# Geiger_v3.net
KiCad netlist of a schematic drawn in EAGLE
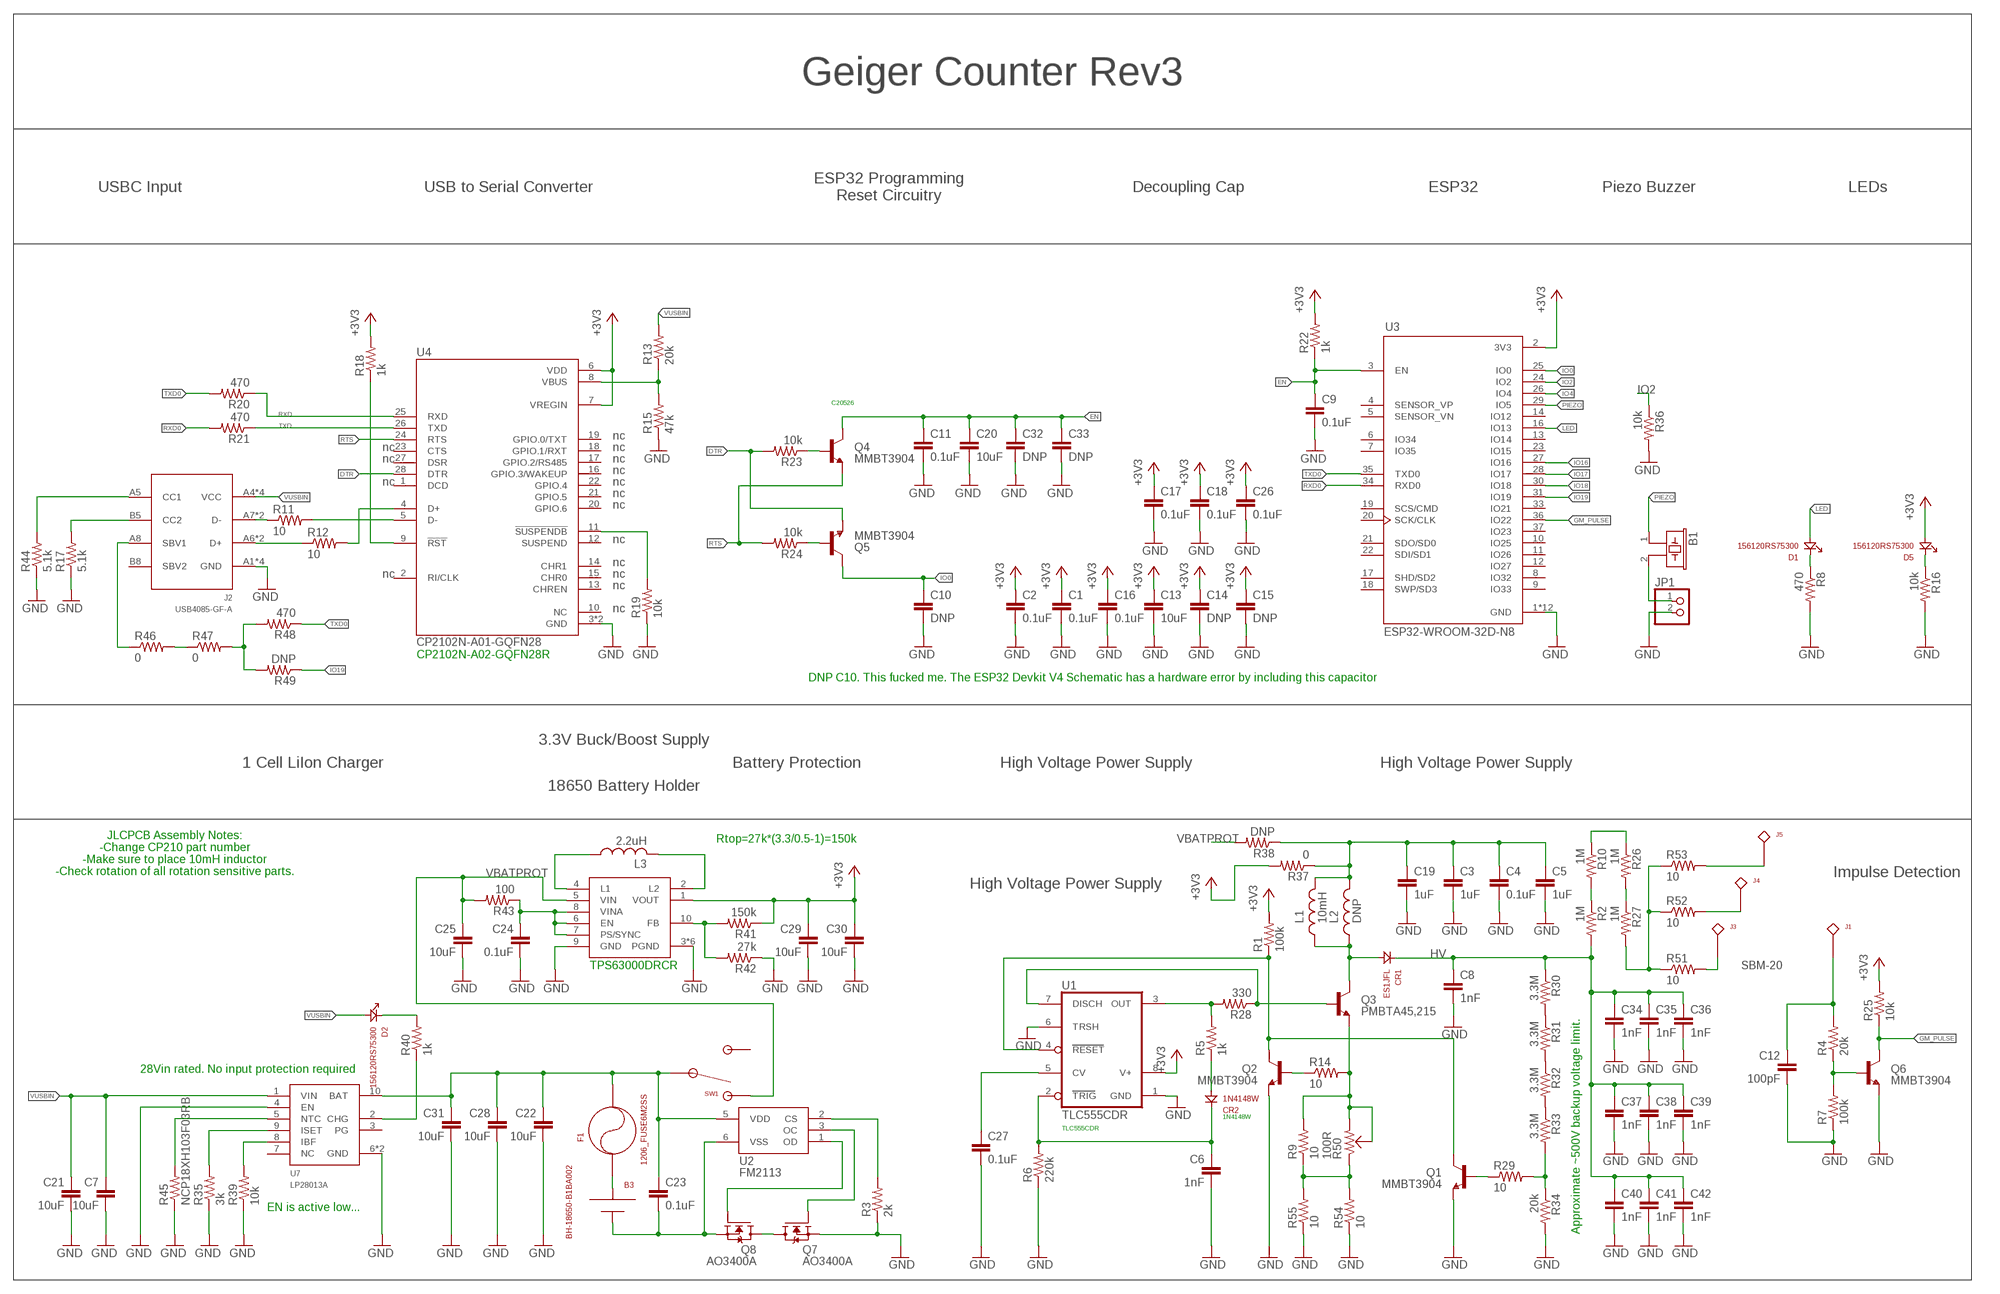
[diagram p0: schematic, sheet 1]

(export (version "E")
  (design (tool "Eeschema 10.0.6"))
  (components
    (comp (ref "B1")
      (value "PIEZO17MM")
      (footprint "eagle-import:PS1740P02E")
      (libsource (lib "eagle-import") (part "PIEZO17MM"))
    )
    (comp (ref "B3")
      (value "BH-18650-B1BA002")
      (footprint "eagle-import:18650")
      (libsource (lib "eagle-import") (part "BH-18650-B1BA002"))
    )
    (comp (ref "C1")
      (value "0.1uF")
      (footprint "eagle-import:0603")
      (libsource (lib "eagle-import") (part "0603_CAPACITOR"))
    )
    (comp (ref "C2")
      (value "0.1uF")
      (footprint "eagle-import:0603")
      (libsource (lib "eagle-import") (part "0603_CAPACITOR"))
    )
    (comp (ref "C3")
      (value "1uF")
      (footprint "eagle-import:0603")
      (libsource (lib "eagle-import") (part "0603_CAPACITOR"))
    )
    (comp (ref "C4")
      (value "0.1uF")
      (footprint "eagle-import:0603")
      (libsource (lib "eagle-import") (part "0603_CAPACITOR"))
    )
    (comp (ref "C5")
      (value "1uF")
      (footprint "eagle-import:0603")
      (libsource (lib "eagle-import") (part "0603_CAPACITOR"))
    )
    (comp (ref "C6")
      (value "1nF")
      (footprint "eagle-import:0603")
      (libsource (lib "eagle-import") (part "0603_CAPACITOR"))
    )
    (comp (ref "C7")
      (value "10uF")
      (footprint "eagle-import:0603")
      (libsource (lib "eagle-import") (part "0603_CAPACITOR"))
    )
    (comp (ref "C8")
      (value "1nF")
      (footprint "eagle-import:1206")
      (libsource (lib "eagle-import") (part "1206_CAPACITOR"))
    )
    (comp (ref "C9")
      (value "0.1uF")
      (footprint "eagle-import:0603")
      (libsource (lib "eagle-import") (part "0603_CAPACITOR"))
    )
    (comp (ref "C10")
      (value "DNP")
      (footprint "eagle-import:0603")
      (libsource (lib "eagle-import") (part "0603_CAPACITOR"))
    )
    (comp (ref "C11")
      (value "0.1uF")
      (footprint "eagle-import:0603")
      (libsource (lib "eagle-import") (part "0603_CAPACITOR"))
    )
    (comp (ref "C12")
      (value "100pF")
      (footprint "eagle-import:0603")
      (libsource (lib "eagle-import") (part "0603_CAPACITOR"))
    )
    (comp (ref "C13")
      (value "10uF")
      (footprint "eagle-import:0603")
      (libsource (lib "eagle-import") (part "0603_CAPACITOR"))
    )
    (comp (ref "C14")
      (value "DNP")
      (footprint "eagle-import:0603")
      (libsource (lib "eagle-import") (part "0603_CAPACITOR"))
    )
    (comp (ref "C15")
      (value "DNP")
      (footprint "eagle-import:0603")
      (libsource (lib "eagle-import") (part "0603_CAPACITOR"))
    )
    (comp (ref "C16")
      (value "0.1uF")
      (footprint "eagle-import:0603")
      (libsource (lib "eagle-import") (part "0603_CAPACITOR"))
    )
    (comp (ref "C17")
      (value "0.1uF")
      (footprint "eagle-import:0603")
      (libsource (lib "eagle-import") (part "0603_CAPACITOR"))
    )
    (comp (ref "C18")
      (value "0.1uF")
      (footprint "eagle-import:0603")
      (libsource (lib "eagle-import") (part "0603_CAPACITOR"))
    )
    (comp (ref "C19")
      (value "1uF")
      (footprint "eagle-import:0603")
      (libsource (lib "eagle-import") (part "0603_CAPACITOR"))
    )
    (comp (ref "C20")
      (value "10uF")
      (footprint "eagle-import:0603")
      (libsource (lib "eagle-import") (part "0603_CAPACITOR"))
    )
    (comp (ref "C21")
      (value "10uF")
      (footprint "eagle-import:0603")
      (libsource (lib "eagle-import") (part "0603_CAPACITOR"))
    )
    (comp (ref "C22")
      (value "10uF")
      (footprint "eagle-import:0603")
      (libsource (lib "eagle-import") (part "0603_CAPACITOR"))
    )
    (comp (ref "C23")
      (value "0.1uF")
      (footprint "eagle-import:0603")
      (libsource (lib "eagle-import") (part "0603_CAPACITOR"))
    )
    (comp (ref "C24")
      (value "0.1uF")
      (footprint "eagle-import:0603")
      (libsource (lib "eagle-import") (part "0603_CAPACITOR"))
    )
    (comp (ref "C25")
      (value "10uF")
      (footprint "eagle-import:0603")
      (libsource (lib "eagle-import") (part "0603_CAPACITOR"))
    )
    (comp (ref "C26")
      (value "0.1uF")
      (footprint "eagle-import:0603")
      (libsource (lib "eagle-import") (part "0603_CAPACITOR"))
    )
    (comp (ref "C27")
      (value "0.1uF")
      (footprint "eagle-import:0603")
      (libsource (lib "eagle-import") (part "0603_CAPACITOR"))
    )
    (comp (ref "C28")
      (value "10uF")
      (footprint "eagle-import:0603")
      (libsource (lib "eagle-import") (part "0603_CAPACITOR"))
    )
    (comp (ref "C29")
      (value "10uF")
      (footprint "eagle-import:0603")
      (libsource (lib "eagle-import") (part "0603_CAPACITOR"))
    )
    (comp (ref "C30")
      (value "10uF")
      (footprint "eagle-import:0603")
      (libsource (lib "eagle-import") (part "0603_CAPACITOR"))
    )
    (comp (ref "C31")
      (value "10uF")
      (footprint "eagle-import:0603")
      (libsource (lib "eagle-import") (part "0603_CAPACITOR"))
    )
    (comp (ref "C32")
      (value "DNP")
      (footprint "eagle-import:0603")
      (libsource (lib "eagle-import") (part "0603_CAPACITOR"))
    )
    (comp (ref "C33")
      (value "DNP")
      (footprint "eagle-import:0603")
      (libsource (lib "eagle-import") (part "0603_CAPACITOR"))
    )
    (comp (ref "C34")
      (value "1nF")
      (footprint "eagle-import:1206")
      (libsource (lib "eagle-import") (part "1206_CAPACITOR"))
    )
    (comp (ref "C35")
      (value "1nF")
      (footprint "eagle-import:1206")
      (libsource (lib "eagle-import") (part "1206_CAPACITOR"))
    )
    (comp (ref "C36")
      (value "1nF")
      (footprint "eagle-import:1206")
      (libsource (lib "eagle-import") (part "1206_CAPACITOR"))
    )
    (comp (ref "C37")
      (value "1nF")
      (footprint "eagle-import:1206")
      (libsource (lib "eagle-import") (part "1206_CAPACITOR"))
    )
    (comp (ref "C38")
      (value "1nF")
      (footprint "eagle-import:1206")
      (libsource (lib "eagle-import") (part "1206_CAPACITOR"))
    )
    (comp (ref "C39")
      (value "1nF")
      (footprint "eagle-import:1206")
      (libsource (lib "eagle-import") (part "1206_CAPACITOR"))
    )
    (comp (ref "C40")
      (value "1nF")
      (footprint "eagle-import:1206")
      (libsource (lib "eagle-import") (part "1206_CAPACITOR"))
    )
    (comp (ref "C41")
      (value "1nF")
      (footprint "eagle-import:1206")
      (libsource (lib "eagle-import") (part "1206_CAPACITOR"))
    )
    (comp (ref "C42")
      (value "1nF")
      (footprint "eagle-import:1206")
      (libsource (lib "eagle-import") (part "1206_CAPACITOR"))
    )
    (comp (ref "CR1")
      (value "ES1JFL")
      (footprint "eagle-import:SOD123(AK)")
      (fields (field (name "PARTNO") "ES1JFLCT-ND"))
      (libsource (lib "eagle-import") (part "ES1JFL"))
    )
    (comp (ref "CR2")
      (value "1N4148W")
      (footprint "eagle-import:SOD123")
      (fields (field (name "PARTNO") "1727-7323-1-ND"))
      (libsource (lib "eagle-import") (part "BAS21GWX"))
    )
    (comp (ref "D1")
      (value "156120RS75300")
      (footprint "eagle-import:1206_REV")
      (fields (field (name "PARTNO") "732-5031-1-ND"))
      (libsource (lib "eagle-import") (part "156120RS75300"))
    )
    (comp (ref "D2")
      (value "156120RS75300")
      (footprint "eagle-import:1206_REV")
      (fields (field (name "PARTNO") "732-5031-1-ND"))
      (libsource (lib "eagle-import") (part "156120RS75300"))
    )
    (comp (ref "D5")
      (value "156120RS75300")
      (footprint "eagle-import:1206_REV")
      (fields (field (name "PARTNO") "732-5031-1-ND"))
      (libsource (lib "eagle-import") (part "156120RS75300"))
    )
    (comp (ref "F1")
      (value "1206_FUSE6M2SS")
      (footprint "eagle-import:1206_FUSE_6M2_SS")
      (libsource (lib "eagle-import") (part "1206_FUSE6M2SS"))
    )
    (comp (ref "J1")
      (value "01010002Z")
      (footprint "eagle-import:01010002Z")
      (fields (field (name "PARTNO") "F4080-ND"))
      (libsource (lib "eagle-import") (part "01010002Z"))
    )
    (comp (ref "J2")
      (value "USB4085-GF-A")
      (footprint "eagle-import:USBC")
      (fields (field (name "PARTNO") "2073-USB4085-GF-ACT-ND"))
      (libsource (lib "eagle-import") (part "USB4085-GF-A"))
    )
    (comp (ref "J3")
      (value "01010002Z")
      (footprint "eagle-import:01010002Z")
      (fields (field (name "PARTNO") "F4080-ND"))
      (libsource (lib "eagle-import") (part "01010002Z"))
    )
    (comp (ref "J4")
      (value "01010002Z")
      (footprint "eagle-import:01010002Z")
      (fields (field (name "PARTNO") "F4080-ND"))
      (libsource (lib "eagle-import") (part "01010002Z"))
    )
    (comp (ref "J5")
      (value "01010002Z")
      (footprint "eagle-import:01010002Z")
      (fields (field (name "PARTNO") "F4080-ND"))
      (libsource (lib "eagle-import") (part "01010002Z"))
    )
    (comp (ref "JP1")
      (value "PINHD-1X2")
      (footprint "eagle-import:1X02")
      (libsource (lib "eagle-import") (part "PINHD-1X2"))
    )
    (comp (ref "L1")
      (value "10mH")
      (footprint "eagle-import:FNR8065S")
      (libsource (lib "eagle-import") (part "FNR8065S103MT"))
    )
    (comp (ref "L2")
      (value "DNP")
      (footprint "eagle-import:SDR1005")
      (fields (field (name "PARTNO") "SDR1005-103KLCT-ND"))
      (libsource (lib "eagle-import") (part "SDR1005-103KL"))
    )
    (comp (ref "L3")
      (value "2.2uH")
      (footprint "eagle-import:CY43")
      (libsource (lib "eagle-import") (part "CY43-2.2UH"))
    )
    (comp (ref "Q1")
      (value "MMBT3904")
      (footprint "eagle-import:SOT23-3_CENTERED")
      (libsource (lib "eagle-import") (part "MMBT3904-TPCENTERED"))
    )
    (comp (ref "Q2")
      (value "MMBT3904")
      (footprint "eagle-import:SOT23-3_CENTERED")
      (libsource (lib "eagle-import") (part "MMBT3904-TPCENTERED"))
    )
    (comp (ref "Q3")
      (value "PMBTA45,215")
      (footprint "eagle-import:SOT23-3")
      (fields (field (name "PARTNO") "1727-5332-1-ND"))
      (libsource (lib "eagle-import") (part "PMBTA45,215"))
    )
    (comp (ref "Q4")
      (value "MMBT3904")
      (footprint "eagle-import:SOT23-3_CENTERED")
      (libsource (lib "eagle-import") (part "MMBT3904-TPCENTERED"))
    )
    (comp (ref "Q5")
      (value "MMBT3904")
      (footprint "eagle-import:SOT23-3_CENTERED")
      (libsource (lib "eagle-import") (part "MMBT3904-TPCENTERED"))
    )
    (comp (ref "Q6")
      (value "MMBT3904")
      (footprint "eagle-import:SOT23-3_CENTERED")
      (libsource (lib "eagle-import") (part "MMBT3904-TPCENTERED"))
    )
    (comp (ref "Q7")
      (value "AO3400A")
      (footprint "eagle-import:SOT23-3_CENTERED")
      (libsource (lib "eagle-import") (part "AO3400A"))
    )
    (comp (ref "Q8")
      (value "AO3400A")
      (footprint "eagle-import:SOT23-3_CENTERED")
      (libsource (lib "eagle-import") (part "AO3400A"))
    )
    (comp (ref "R1")
      (value "100k")
      (footprint "eagle-import:0603")
      (libsource (lib "eagle-import") (part "0603_RESISTOR"))
    )
    (comp (ref "R2")
      (value "1M")
      (footprint "eagle-import:0603")
      (libsource (lib "eagle-import") (part "0603_RESISTOR"))
    )
    (comp (ref "R3")
      (value "2k")
      (footprint "eagle-import:0603")
      (libsource (lib "eagle-import") (part "0603_RESISTOR"))
    )
    (comp (ref "R4")
      (value "20k")
      (footprint "eagle-import:0603")
      (libsource (lib "eagle-import") (part "0603_RESISTOR"))
    )
    (comp (ref "R5")
      (value "1k")
      (footprint "eagle-import:0603")
      (libsource (lib "eagle-import") (part "0603_RESISTOR"))
    )
    (comp (ref "R6")
      (value "220k")
      (footprint "eagle-import:0603")
      (libsource (lib "eagle-import") (part "0603_RESISTOR"))
    )
    (comp (ref "R7")
      (value "100k")
      (footprint "eagle-import:0603")
      (libsource (lib "eagle-import") (part "0603_RESISTOR"))
    )
    (comp (ref "R8")
      (value "470")
      (footprint "eagle-import:0603")
      (libsource (lib "eagle-import") (part "0603_RESISTOR"))
    )
    (comp (ref "R9")
      (value "10")
      (footprint "eagle-import:0603")
      (libsource (lib "eagle-import") (part "0603_RESISTOR"))
    )
    (comp (ref "R10")
      (value "1M")
      (footprint "eagle-import:0603")
      (libsource (lib "eagle-import") (part "0603_RESISTOR"))
    )
    (comp (ref "R11")
      (value "10")
      (footprint "eagle-import:0603")
      (libsource (lib "eagle-import") (part "0603_RESISTOR"))
    )
    (comp (ref "R12")
      (value "10")
      (footprint "eagle-import:0603")
      (libsource (lib "eagle-import") (part "0603_RESISTOR"))
    )
    (comp (ref "R13")
      (value "20k")
      (footprint "eagle-import:0603")
      (libsource (lib "eagle-import") (part "0603_RESISTOR"))
    )
    (comp (ref "R14")
      (value "10")
      (footprint "eagle-import:0603")
      (libsource (lib "eagle-import") (part "0603_RESISTOR"))
    )
    (comp (ref "R15")
      (value "47k")
      (footprint "eagle-import:0603")
      (libsource (lib "eagle-import") (part "0603_RESISTOR"))
    )
    (comp (ref "R16")
      (value "10k")
      (footprint "eagle-import:0603")
      (libsource (lib "eagle-import") (part "0603_RESISTOR"))
    )
    (comp (ref "R17")
      (value "5.1k")
      (footprint "eagle-import:0603")
      (libsource (lib "eagle-import") (part "0603_RESISTOR"))
    )
    (comp (ref "R18")
      (value "1k")
      (footprint "eagle-import:0603")
      (libsource (lib "eagle-import") (part "0603_RESISTOR"))
    )
    (comp (ref "R19")
      (value "10k")
      (footprint "eagle-import:0603")
      (libsource (lib "eagle-import") (part "0603_RESISTOR"))
    )
    (comp (ref "R20")
      (value "470")
      (footprint "eagle-import:0603")
      (libsource (lib "eagle-import") (part "0603_RESISTOR"))
    )
    (comp (ref "R21")
      (value "470")
      (footprint "eagle-import:0603")
      (libsource (lib "eagle-import") (part "0603_RESISTOR"))
    )
    (comp (ref "R22")
      (value "1k")
      (footprint "eagle-import:0603")
      (libsource (lib "eagle-import") (part "0603_RESISTOR"))
    )
    (comp (ref "R23")
      (value "10k")
      (footprint "eagle-import:0603")
      (libsource (lib "eagle-import") (part "0603_RESISTOR"))
    )
    (comp (ref "R24")
      (value "10k")
      (footprint "eagle-import:0603")
      (libsource (lib "eagle-import") (part "0603_RESISTOR"))
    )
    (comp (ref "R25")
      (value "10k")
      (footprint "eagle-import:0603")
      (libsource (lib "eagle-import") (part "0603_RESISTOR"))
    )
    (comp (ref "R26")
      (value "1M")
      (footprint "eagle-import:0603")
      (libsource (lib "eagle-import") (part "0603_RESISTOR"))
    )
    (comp (ref "R27")
      (value "1M")
      (footprint "eagle-import:0603")
      (libsource (lib "eagle-import") (part "0603_RESISTOR"))
    )
    (comp (ref "R28")
      (value "330")
      (footprint "eagle-import:0603")
      (libsource (lib "eagle-import") (part "0603_RESISTOR"))
    )
    (comp (ref "R29")
      (value "10")
      (footprint "eagle-import:0603")
      (libsource (lib "eagle-import") (part "0603_RESISTOR"))
    )
    (comp (ref "R30")
      (value "3.3M")
      (footprint "eagle-import:0603")
      (libsource (lib "eagle-import") (part "0603_RESISTOR"))
    )
    (comp (ref "R31")
      (value "3.3M")
      (footprint "eagle-import:0603")
      (libsource (lib "eagle-import") (part "0603_RESISTOR"))
    )
    (comp (ref "R32")
      (value "3.3M")
      (footprint "eagle-import:0603")
      (libsource (lib "eagle-import") (part "0603_RESISTOR"))
    )
    (comp (ref "R33")
      (value "3.3M")
      (footprint "eagle-import:0603")
      (libsource (lib "eagle-import") (part "0603_RESISTOR"))
    )
    (comp (ref "R34")
      (value "20k")
      (footprint "eagle-import:0603")
      (libsource (lib "eagle-import") (part "0603_RESISTOR"))
    )
    (comp (ref "R35")
      (value "3k")
      (footprint "eagle-import:0603")
      (libsource (lib "eagle-import") (part "0603_RESISTOR"))
    )
    (comp (ref "R36")
      (value "10k")
      (footprint "eagle-import:0603")
      (libsource (lib "eagle-import") (part "0603_RESISTOR"))
    )
    (comp (ref "R37")
      (value "0")
      (footprint "eagle-import:0603")
      (libsource (lib "eagle-import") (part "0603_RESISTOR"))
    )
    (comp (ref "R38")
      (value "DNP")
      (footprint "eagle-import:0603")
      (libsource (lib "eagle-import") (part "0603_RESISTOR"))
    )
    (comp (ref "R39")
      (value "10k")
      (footprint "eagle-import:0603")
      (libsource (lib "eagle-import") (part "0603_RESISTOR"))
    )
    (comp (ref "R40")
      (value "1k")
      (footprint "eagle-import:0603")
      (libsource (lib "eagle-import") (part "0603_RESISTOR"))
    )
    (comp (ref "R41")
      (value "150k")
      (footprint "eagle-import:0603")
      (libsource (lib "eagle-import") (part "0603_RESISTOR"))
    )
    (comp (ref "R42")
      (value "27k")
      (footprint "eagle-import:0603")
      (libsource (lib "eagle-import") (part "0603_RESISTOR"))
    )
    (comp (ref "R43")
      (value "100")
      (footprint "eagle-import:0603")
      (libsource (lib "eagle-import") (part "0603_RESISTOR"))
    )
    (comp (ref "R44")
      (value "5.1k")
      (footprint "eagle-import:0603")
      (libsource (lib "eagle-import") (part "0603_RESISTOR"))
    )
    (comp (ref "R45")
      (value "NCP18XH103F03RB")
      (footprint "eagle-import:0603")
      (libsource (lib "eagle-import") (part "0603_RESISTOR"))
    )
    (comp (ref "R46")
      (value "0")
      (footprint "eagle-import:1206")
      (libsource (lib "eagle-import") (part "1206_RESISTOR"))
    )
    (comp (ref "R47")
      (value "0")
      (footprint "eagle-import:1206")
      (libsource (lib "eagle-import") (part "1206_RESISTOR"))
    )
    (comp (ref "R48")
      (value "470")
      (footprint "eagle-import:0603")
      (libsource (lib "eagle-import") (part "0603_RESISTOR"))
    )
    (comp (ref "R49")
      (value "DNP")
      (footprint "eagle-import:0603")
      (libsource (lib "eagle-import") (part "0603_RESISTOR"))
    )
    (comp (ref "R50")
      (value "100R")
      (footprint "eagle-import:ST-4")
      (libsource (lib "eagle-import") (part "ST-4ETB101"))
    )
    (comp (ref "R51")
      (value "10")
      (footprint "eagle-import:0603")
      (libsource (lib "eagle-import") (part "0603_RESISTOR"))
    )
    (comp (ref "R52")
      (value "10")
      (footprint "eagle-import:0603")
      (libsource (lib "eagle-import") (part "0603_RESISTOR"))
    )
    (comp (ref "R53")
      (value "10")
      (footprint "eagle-import:0603")
      (libsource (lib "eagle-import") (part "0603_RESISTOR"))
    )
    (comp (ref "R54")
      (value "10")
      (footprint "eagle-import:0603")
      (libsource (lib "eagle-import") (part "0603_RESISTOR"))
    )
    (comp (ref "R55")
      (value "10")
      (footprint "eagle-import:0603")
      (libsource (lib "eagle-import") (part "0603_RESISTOR"))
    )
    (comp (ref "SW1")
      (value "SPDT")
      (footprint "eagle-import:TOGGLE_RA")
      (fields (field (name "PARTNO") "EG2362-ND"))
      (libsource (lib "eagle-import") (part "100SP1T2B4M6QE"))
    )
    (comp (ref "U1")
      (value "TLC555CDR")
      (footprint "eagle-import:SOIC8")
      (fields (field (name "PARTNO") "296-52992-ND"))
      (libsource (lib "eagle-import") (part "TLC555CDG4"))
    )
    (comp (ref "U2")
      (value "FM2113")
      (footprint "eagle-import:SOT23-6")
      (libsource (lib "eagle-import") (part "FM2113"))
    )
    (comp (ref "U3")
      (value "ESP32-WROOM-32D-N8")
      (footprint "eagle-import:MODULE_ESP32-WROOM-32D")
      (fields (field (name "MF") "Espressif Systems") (field (name "MP") "ESP32-WROOM-32D"))
      (libsource (lib "eagle-import") (part "ESP32-WROOM-32D"))
    )
    (comp (ref "U4")
      (value "CP2102N-A01-GQFN28")
      (footprint "eagle-import:QFN50P500X500X80-29N")
      (fields (field (name "MF") "Silicon Labs"))
      (libsource (lib "eagle-import") (part "CP2102N-A01-GQFN28"))
    )
    (comp (ref "U6")
      (value "TPS63000DRCR")
      (footprint "eagle-import:S-PVSON-N10")
      (fields (field (name "PARTNO") "296-19641-1-ND"))
      (libsource (lib "eagle-import") (part "TPS63000DRCR"))
    )
    (comp (ref "U7")
      (value "LP28013A")
      (footprint "eagle-import:10DFN")
      (libsource (lib "eagle-import") (part "LP28013A"))
    )
  )
  (nets
    (net (code "1") (name "+3V3") (class "Default")
      (node (ref "C1") (pin "1") (pinfunction "1_1") (pintype "passive"))
      (node (ref "C13") (pin "1") (pinfunction "1_1") (pintype "passive"))
      (node (ref "C14") (pin "1") (pinfunction "1_1") (pintype "passive"))
      (node (ref "C15") (pin "1") (pinfunction "1_1") (pintype "passive"))
      (node (ref "C16") (pin "1") (pinfunction "1_1") (pintype "passive"))
      (node (ref "C17") (pin "1") (pinfunction "1_1") (pintype "passive"))
      (node (ref "C18") (pin "1") (pinfunction "1_1") (pintype "passive"))
      (node (ref "C2") (pin "1") (pinfunction "1_1") (pintype "passive"))
      (node (ref "C26") (pin "1") (pinfunction "1_1") (pintype "passive"))
      (node (ref "C29") (pin "1") (pinfunction "1_1") (pintype "passive"))
      (node (ref "C30") (pin "1") (pinfunction "1_1") (pintype "passive"))
      (node (ref "D5") (pin "A") (pinfunction "A_A") (pintype "bidirectional"))
      (node (ref "R1") (pin "2") (pinfunction "2_2") (pintype "passive"))
      (node (ref "R18") (pin "2") (pinfunction "2_2") (pintype "passive"))
      (node (ref "R22") (pin "2") (pinfunction "2_2") (pintype "passive"))
      (node (ref "R25") (pin "2") (pinfunction "2_2") (pintype "passive"))
      (node (ref "R37") (pin "2") (pinfunction "2_2") (pintype "passive"))
      (node (ref "R41") (pin "1") (pinfunction "1_1") (pintype "passive"))
      (node (ref "U1") (pin "8") (pinfunction "V+_8") (pintype "power_in"))
      (node (ref "U3") (pin "2") (pinfunction "3V3_2") (pintype "power_in"))
      (node (ref "U4") (pin "6") (pinfunction "VDD_6") (pintype "power_in"))
      (node (ref "U4") (pin "7") (pinfunction "VREGIN_7") (pintype "power_in"))
      (node (ref "U6") (pin "1") (pinfunction "VOUT_1") (pintype "bidirectional"))
    )
    (net (code "2") (name "/HV") (class "Default")
      (node (ref "C34") (pin "1") (pinfunction "1_1") (pintype "passive"))
      (node (ref "C35") (pin "1") (pinfunction "1_1") (pintype "passive"))
      (node (ref "C36") (pin "1") (pinfunction "1_1") (pintype "passive"))
      (node (ref "C37") (pin "1") (pinfunction "1_1") (pintype "passive"))
      (node (ref "C38") (pin "1") (pinfunction "1_1") (pintype "passive"))
      (node (ref "C39") (pin "1") (pinfunction "1_1") (pintype "passive"))
      (node (ref "C40") (pin "1") (pinfunction "1_1") (pintype "passive"))
      (node (ref "C41") (pin "1") (pinfunction "1_1") (pintype "passive"))
      (node (ref "C42") (pin "1") (pinfunction "1_1") (pintype "passive"))
      (node (ref "C8") (pin "1") (pinfunction "1_1") (pintype "passive"))
      (node (ref "CR1") (pin "K") (pinfunction "K_K") (pintype "bidirectional"))
      (node (ref "R2") (pin "2") (pinfunction "2_2") (pintype "passive"))
      (node (ref "R30") (pin "1") (pinfunction "1_1") (pintype "passive"))
    )
    (net (code "3") (name "/RXD") (class "Default")
      (node (ref "R20") (pin "1") (pinfunction "1_1") (pintype "passive"))
      (node (ref "U4") (pin "25") (pinfunction "RXD_25") (pintype "input"))
    )
    (net (code "4") (name "/TXD") (class "Default")
      (node (ref "R21") (pin "1") (pinfunction "1_1") (pintype "passive"))
      (node (ref "U4") (pin "26") (pinfunction "TXD_26") (pintype "output"))
    )
    (net (code "5") (name "/VBATPROT") (class "Default")
      (node (ref "C25") (pin "1") (pinfunction "1_1") (pintype "passive"))
      (node (ref "R38") (pin "2") (pinfunction "2_2") (pintype "passive"))
      (node (ref "R43") (pin "2") (pinfunction "2_2") (pintype "passive"))
      (node (ref "SW1") (pin "3") (pinfunction "P$3_3") (pintype "bidirectional"))
      (node (ref "U6") (pin "5") (pinfunction "VIN_5") (pintype "bidirectional"))
    )
    (net (code "6") (name "DTR") (class "Default")
      (node (ref "Q5") (pin "2") (pinfunction "E_2") (pintype "passive"))
      (node (ref "R23") (pin "2") (pinfunction "2_2") (pintype "passive"))
      (node (ref "U4") (pin "28") (pinfunction "DTR_28") (pintype "output"))
    )
    (net (code "7") (name "EN") (class "Default")
      (node (ref "C11") (pin "1") (pinfunction "1_1") (pintype "passive"))
      (node (ref "C20") (pin "1") (pinfunction "1_1") (pintype "passive"))
      (node (ref "C32") (pin "1") (pinfunction "1_1") (pintype "passive"))
      (node (ref "C33") (pin "1") (pinfunction "1_1") (pintype "passive"))
      (node (ref "C9") (pin "1") (pinfunction "1_1") (pintype "passive"))
      (node (ref "Q4") (pin "3") (pinfunction "C_3") (pintype "passive"))
      (node (ref "R22") (pin "1") (pinfunction "1_1") (pintype "passive"))
      (node (ref "U3") (pin "3") (pinfunction "EN_3") (pintype "input"))
    )
    (net (code "8") (name "GM_PULSE") (class "Default")
      (node (ref "Q6") (pin "3") (pinfunction "C_3") (pintype "passive"))
      (node (ref "R25") (pin "1") (pinfunction "1_1") (pintype "passive"))
      (node (ref "U3") (pin "36") (pinfunction "IO22_36") (pintype "bidirectional"))
    )
    (net (code "9") (name "GND") (class "Default")
      (node (ref "C1") (pin "2") (pinfunction "2_2") (pintype "passive"))
      (node (ref "C10") (pin "2") (pinfunction "2_2") (pintype "passive"))
      (node (ref "C11") (pin "2") (pinfunction "2_2") (pintype "passive"))
      (node (ref "C12") (pin "2") (pinfunction "2_2") (pintype "passive"))
      (node (ref "C13") (pin "2") (pinfunction "2_2") (pintype "passive"))
      (node (ref "C14") (pin "2") (pinfunction "2_2") (pintype "passive"))
      (node (ref "C15") (pin "2") (pinfunction "2_2") (pintype "passive"))
      (node (ref "C16") (pin "2") (pinfunction "2_2") (pintype "passive"))
      (node (ref "C17") (pin "2") (pinfunction "2_2") (pintype "passive"))
      (node (ref "C18") (pin "2") (pinfunction "2_2") (pintype "passive"))
      (node (ref "C19") (pin "2") (pinfunction "2_2") (pintype "passive"))
      (node (ref "C2") (pin "2") (pinfunction "2_2") (pintype "passive"))
      (node (ref "C20") (pin "2") (pinfunction "2_2") (pintype "passive"))
      (node (ref "C21") (pin "2") (pinfunction "2_2") (pintype "passive"))
      (node (ref "C22") (pin "2") (pinfunction "2_2") (pintype "passive"))
      (node (ref "C24") (pin "2") (pinfunction "2_2") (pintype "passive"))
      (node (ref "C25") (pin "2") (pinfunction "2_2") (pintype "passive"))
      (node (ref "C26") (pin "2") (pinfunction "2_2") (pintype "passive"))
      (node (ref "C27") (pin "2") (pinfunction "2_2") (pintype "passive"))
      (node (ref "C28") (pin "2") (pinfunction "2_2") (pintype "passive"))
      (node (ref "C29") (pin "2") (pinfunction "2_2") (pintype "passive"))
      (node (ref "C3") (pin "2") (pinfunction "2_2") (pintype "passive"))
      (node (ref "C30") (pin "2") (pinfunction "2_2") (pintype "passive"))
      (node (ref "C31") (pin "2") (pinfunction "2_2") (pintype "passive"))
      (node (ref "C32") (pin "2") (pinfunction "2_2") (pintype "passive"))
      (node (ref "C33") (pin "2") (pinfunction "2_2") (pintype "passive"))
      (node (ref "C34") (pin "2") (pinfunction "2_2") (pintype "passive"))
      (node (ref "C35") (pin "2") (pinfunction "2_2") (pintype "passive"))
      (node (ref "C36") (pin "2") (pinfunction "2_2") (pintype "passive"))
      (node (ref "C37") (pin "2") (pinfunction "2_2") (pintype "passive"))
      (node (ref "C38") (pin "2") (pinfunction "2_2") (pintype "passive"))
      (node (ref "C39") (pin "2") (pinfunction "2_2") (pintype "passive"))
      (node (ref "C4") (pin "2") (pinfunction "2_2") (pintype "passive"))
      (node (ref "C40") (pin "2") (pinfunction "2_2") (pintype "passive"))
      (node (ref "C41") (pin "2") (pinfunction "2_2") (pintype "passive"))
      (node (ref "C42") (pin "2") (pinfunction "2_2") (pintype "passive"))
      (node (ref "C5") (pin "2") (pinfunction "2_2") (pintype "passive"))
      (node (ref "C6") (pin "2") (pinfunction "2_2") (pintype "passive"))
      (node (ref "C7") (pin "2") (pinfunction "2_2") (pintype "passive"))
      (node (ref "C8") (pin "2") (pinfunction "2_2") (pintype "passive"))
      (node (ref "C9") (pin "2") (pinfunction "2_2") (pintype "passive"))
      (node (ref "J2") (pin "A1") (pinfunction "GND_A1") (pintype "bidirectional"))
      (node (ref "J2") (pin "A12") (pinfunction "GND_A12") (pintype "bidirectional"))
      (node (ref "J2") (pin "B1") (pinfunction "GND_B1") (pintype "bidirectional"))
      (node (ref "J2") (pin "B12") (pinfunction "GND_B12") (pintype "bidirectional"))
      (node (ref "JP1") (pin "2") (pinfunction "2_2") (pintype "passive"))
      (node (ref "Q1") (pin "2") (pinfunction "E_2") (pintype "passive"))
      (node (ref "Q2") (pin "2") (pinfunction "E_2") (pintype "passive"))
      (node (ref "Q6") (pin "2") (pinfunction "E_2") (pintype "passive"))
      (node (ref "Q7") (pin "2") (pinfunction "S_2") (pintype "passive"))
      (node (ref "R15") (pin "1") (pinfunction "1_1") (pintype "passive"))
      (node (ref "R16") (pin "2") (pinfunction "2_2") (pintype "passive"))
      (node (ref "R17") (pin "1") (pinfunction "1_1") (pintype "passive"))
      (node (ref "R19") (pin "1") (pinfunction "1_1") (pintype "passive"))
      (node (ref "R3") (pin "1") (pinfunction "1_1") (pintype "passive"))
      (node (ref "R34") (pin "2") (pinfunction "2_2") (pintype "passive"))
      (node (ref "R35") (pin "1") (pinfunction "1_1") (pintype "passive"))
      (node (ref "R36") (pin "2") (pinfunction "2_2") (pintype "passive"))
      (node (ref "R39") (pin "1") (pinfunction "1_1") (pintype "passive"))
      (node (ref "R42") (pin "1") (pinfunction "1_1") (pintype "passive"))
      (node (ref "R44") (pin "1") (pinfunction "1_1") (pintype "passive"))
      (node (ref "R45") (pin "1") (pinfunction "1_1") (pintype "passive"))
      (node (ref "R54") (pin "1") (pinfunction "1_1") (pintype "passive"))
      (node (ref "R55") (pin "1") (pinfunction "1_1") (pintype "passive"))
      (node (ref "R6") (pin "1") (pinfunction "1_1") (pintype "passive"))
      (node (ref "R7") (pin "1") (pinfunction "1_1") (pintype "passive"))
      (node (ref "R8") (pin "2") (pinfunction "2_2") (pintype "passive"))
      (node (ref "U1") (pin "1") (pinfunction "GND_1") (pintype "power_in"))
      (node (ref "U1") (pin "6") (pinfunction "TRSH_6") (pintype "input"))
      (node (ref "U3") (pin "1") (pinfunction "GND_1") (pintype "power_in"))
      (node (ref "U3") (pin "15") (pinfunction "GND_15") (pintype "power_in"))
      (node (ref "U3") (pin "38") (pinfunction "GND_38") (pintype "power_in"))
      (node (ref "U3") (pin "39_1") (pinfunction "GND_39_1") (pintype "power_in"))
      (node (ref "U3") (pin "39_2") (pinfunction "GND_39_2") (pintype "power_in"))
      (node (ref "U3") (pin "39_3") (pinfunction "GND_39_3") (pintype "power_in"))
      (node (ref "U3") (pin "39_4") (pinfunction "GND_39_4") (pintype "power_in"))
      (node (ref "U3") (pin "39_5") (pinfunction "GND_39_5") (pintype "power_in"))
      (node (ref "U3") (pin "39_6") (pinfunction "GND_39_6") (pintype "power_in"))
      (node (ref "U3") (pin "39_7") (pinfunction "GND_39_7") (pintype "power_in"))
      (node (ref "U3") (pin "39_8") (pinfunction "GND_39_8") (pintype "power_in"))
      (node (ref "U3") (pin "39_9") (pinfunction "GND_39_9") (pintype "power_in"))
      (node (ref "U4") (pin "29") (pinfunction "GND_29") (pintype "power_in"))
      (node (ref "U4") (pin "3") (pinfunction "GND_3") (pintype "power_in"))
      (node (ref "U6") (pin "3") (pinfunction "PGND_3") (pintype "bidirectional"))
      (node (ref "U6") (pin "9") (pinfunction "GND_9") (pintype "bidirectional"))
      (node (ref "U6") (pin "PG") (pinfunction "PGND_PG") (pintype "bidirectional"))
      (node (ref "U6") (pin "PG1") (pinfunction "PGND_PG1") (pintype "bidirectional"))
      (node (ref "U6") (pin "PG2") (pinfunction "PGND_PG2") (pintype "bidirectional"))
      (node (ref "U6") (pin "PG3") (pinfunction "PGND_PG3") (pintype "bidirectional"))
      (node (ref "U6") (pin "PG4") (pinfunction "PGND_PG4") (pintype "bidirectional"))
      (node (ref "U7") (pin "4") (pinfunction "EN_4") (pintype "bidirectional"))
      (node (ref "U7") (pin "6") (pinfunction "GND_6") (pintype "bidirectional"))
      (node (ref "U7") (pin "GF") (pinfunction "GND_GF") (pintype "bidirectional"))
    )
    (net (code "10") (name "IO0") (class "Default")
      (node (ref "C10") (pin "1") (pinfunction "1_1") (pintype "passive"))
      (node (ref "Q5") (pin "3") (pinfunction "C_3") (pintype "passive"))
      (node (ref "U3") (pin "25") (pinfunction "IO0_25") (pintype "bidirectional"))
    )
    (net (code "11") (name "IO2") (class "Default")
      (node (ref "R36") (pin "1") (pinfunction "1_1") (pintype "passive"))
      (node (ref "U3") (pin "24") (pinfunction "IO2_24") (pintype "bidirectional"))
    )
    (net (code "12") (name "IO4") (class "Default")
      (node (ref "U3") (pin "26") (pinfunction "IO4_26") (pintype "bidirectional"))
    )
    (net (code "13") (name "IO16") (class "Default")
      (node (ref "U3") (pin "27") (pinfunction "IO16_27") (pintype "bidirectional"))
    )
    (net (code "14") (name "IO17") (class "Default")
      (node (ref "U3") (pin "28") (pinfunction "IO17_28") (pintype "bidirectional"))
    )
    (net (code "15") (name "IO18") (class "Default")
      (node (ref "U3") (pin "30") (pinfunction "IO18_30") (pintype "bidirectional"))
    )
    (net (code "16") (name "IO19") (class "Default")
      (node (ref "R49") (pin "1") (pinfunction "1_1") (pintype "passive"))
      (node (ref "U3") (pin "31") (pinfunction "IO19_31") (pintype "bidirectional"))
    )
    (net (code "17") (name "LED") (class "Default")
      (node (ref "D1") (pin "A") (pinfunction "A_A") (pintype "bidirectional"))
      (node (ref "U3") (pin "16") (pinfunction "IO13_16") (pintype "bidirectional"))
    )
    (net (code "18") (name "Net-(B1-Pad2)") (class "Default")
      (node (ref "B1") (pin "2") (pinfunction "2_2") (pintype "passive"))
      (node (ref "JP1") (pin "1") (pinfunction "1_1") (pintype "passive"))
    )
    (net (code "19") (name "Net-(B3-Pad+)") (class "Default")
      (node (ref "B3") (pin "+") (pinfunction "+_+") (pintype "bidirectional"))
      (node (ref "F1") (pin "P$1") (pinfunction "P$1_P$1") (pintype "bidirectional"))
    )
    (net (code "20") (name "Net-(C12-Pad1)") (class "Default")
      (node (ref "C12") (pin "1") (pinfunction "1_1") (pintype "passive"))
      (node (ref "J1") (pin "P$1") (pinfunction "P$1_P$1") (pintype "bidirectional"))
      (node (ref "R4") (pin "2") (pinfunction "2_2") (pintype "passive"))
    )
    (net (code "21") (name "Net-(C19-Pad1)") (class "Default")
      (node (ref "C19") (pin "1") (pinfunction "1_1") (pintype "passive"))
      (node (ref "C3") (pin "1") (pinfunction "1_1") (pintype "passive"))
      (node (ref "C4") (pin "1") (pinfunction "1_1") (pintype "passive"))
      (node (ref "C5") (pin "1") (pinfunction "1_1") (pintype "passive"))
      (node (ref "L1") (pin "P$2") (pinfunction "P$2_P$2") (pintype "bidirectional"))
      (node (ref "L2") (pin "P$2") (pinfunction "P$2_P$2") (pintype "bidirectional"))
      (node (ref "R37") (pin "1") (pinfunction "1_1") (pintype "passive"))
      (node (ref "R38") (pin "1") (pinfunction "1_1") (pintype "passive"))
    )
    (net (code "22") (name "Net-(CR2-A)") (class "Default")
      (node (ref "CR2") (pin "2") (pinfunction "A_2") (pintype "bidirectional"))
      (node (ref "R5") (pin "1") (pinfunction "1_1") (pintype "passive"))
    )
    (net (code "23") (name "Net-(CR2-K)") (class "Default")
      (node (ref "C6") (pin "1") (pinfunction "1_1") (pintype "passive"))
      (node (ref "CR2") (pin "1") (pinfunction "K_1") (pintype "bidirectional"))
      (node (ref "R6") (pin "2") (pinfunction "2_2") (pintype "passive"))
      (node (ref "U1") (pin "2") (pinfunction "TRIG_2") (pintype "bidirectional"))
    )
    (net (code "24") (name "Net-(D1-PadK)") (class "Default")
      (node (ref "D1") (pin "K") (pinfunction "K_K") (pintype "bidirectional"))
      (node (ref "R8") (pin "1") (pinfunction "1_1") (pintype "passive"))
    )
    (net (code "25") (name "Net-(D2-PadK)") (class "Default")
      (node (ref "D2") (pin "K") (pinfunction "K_K") (pintype "bidirectional"))
      (node (ref "R40") (pin "2") (pinfunction "2_2") (pintype "passive"))
    )
    (net (code "26") (name "Net-(D5-PadK)") (class "Default")
      (node (ref "D5") (pin "K") (pinfunction "K_K") (pintype "bidirectional"))
      (node (ref "R16") (pin "1") (pinfunction "1_1") (pintype "passive"))
    )
    (net (code "27") (name "Net-(J2-CC1)") (class "Default")
      (node (ref "J2") (pin "A5") (pinfunction "CC1_A5") (pintype "bidirectional"))
      (node (ref "R44") (pin "2") (pinfunction "2_2") (pintype "passive"))
    )
    (net (code "28") (name "Net-(J2-CC2)") (class "Default")
      (node (ref "J2") (pin "B5") (pinfunction "CC2_B5") (pintype "bidirectional"))
      (node (ref "R17") (pin "2") (pinfunction "2_2") (pintype "passive"))
    )
    (net (code "29") (name "Net-(J2-D+-PadA6)") (class "Default")
      (node (ref "J2") (pin "A6") (pinfunction "D+_A6") (pintype "bidirectional"))
      (node (ref "J2") (pin "B6") (pinfunction "D+_B6") (pintype "bidirectional"))
      (node (ref "R12") (pin "1") (pinfunction "1_1") (pintype "passive"))
    )
    (net (code "30") (name "Net-(J2-D--PadA7)") (class "Default")
      (node (ref "J2") (pin "A7") (pinfunction "D-_A7") (pintype "bidirectional"))
      (node (ref "J2") (pin "B7") (pinfunction "D-_B7") (pintype "bidirectional"))
      (node (ref "R11") (pin "1") (pinfunction "1_1") (pintype "passive"))
    )
    (net (code "31") (name "Net-(J2-SBV1)") (class "Default")
      (node (ref "J2") (pin "A8") (pinfunction "SBV1_A8") (pintype "bidirectional"))
      (node (ref "R46") (pin "1") (pinfunction "1_1") (pintype "passive"))
    )
    (net (code "32") (name "Net-(J3-PadP$1)") (class "Default")
      (node (ref "J3") (pin "P$1") (pinfunction "P$1_P$1") (pintype "bidirectional"))
      (node (ref "R51") (pin "2") (pinfunction "2_2") (pintype "passive"))
    )
    (net (code "33") (name "Net-(J4-PadP$1)") (class "Default")
      (node (ref "J4") (pin "P$1") (pinfunction "P$1_P$1") (pintype "bidirectional"))
      (node (ref "R52") (pin "2") (pinfunction "2_2") (pintype "passive"))
    )
    (net (code "34") (name "Net-(J5-PadP$1)") (class "Default")
      (node (ref "J5") (pin "P$1") (pinfunction "P$1_P$1") (pintype "bidirectional"))
      (node (ref "R53") (pin "2") (pinfunction "2_2") (pintype "passive"))
    )
    (net (code "35") (name "Net-(L3-1)") (class "Default")
      (node (ref "L3") (pin "P$1") (pinfunction "1_P$1") (pintype "passive"))
      (node (ref "U6") (pin "4") (pinfunction "L1_4") (pintype "bidirectional"))
    )
    (net (code "36") (name "Net-(L3-2)") (class "Default")
      (node (ref "L3") (pin "P$2") (pinfunction "2_P$2") (pintype "passive"))
      (node (ref "U6") (pin "2") (pinfunction "L2_2") (pintype "bidirectional"))
    )
    (net (code "37") (name "Net-(Q1-B)") (class "Default")
      (node (ref "Q1") (pin "1") (pinfunction "B_1") (pintype "passive"))
      (node (ref "R29") (pin "1") (pinfunction "1_1") (pintype "passive"))
    )
    (net (code "38") (name "Net-(Q1-C)") (class "Default")
      (node (ref "Q1") (pin "3") (pinfunction "C_3") (pintype "passive"))
      (node (ref "Q2") (pin "3") (pinfunction "C_3") (pintype "passive"))
      (node (ref "R1") (pin "1") (pinfunction "1_1") (pintype "passive"))
      (node (ref "U1") (pin "4") (pinfunction "RESET_4") (pintype "input"))
    )
    (net (code "39") (name "Net-(Q2-B)") (class "Default")
      (node (ref "Q2") (pin "1") (pinfunction "B_1") (pintype "passive"))
      (node (ref "R14") (pin "1") (pinfunction "1_1") (pintype "passive"))
    )
    (net (code "40") (name "Net-(Q3-B)") (class "Default")
      (node (ref "Q3") (pin "1") (pinfunction "B_1") (pintype "passive"))
      (node (ref "R28") (pin "1") (pinfunction "1_1") (pintype "passive"))
      (node (ref "U1") (pin "7") (pinfunction "DISCH_7") (pintype "input"))
    )
    (net (code "41") (name "Net-(Q3-C)") (class "Default")
      (node (ref "CR1") (pin "A") (pinfunction "A_A") (pintype "bidirectional"))
      (node (ref "L1") (pin "P$1") (pinfunction "P$1_P$1") (pintype "bidirectional"))
      (node (ref "L2") (pin "P$1") (pinfunction "P$1_P$1") (pintype "bidirectional"))
      (node (ref "Q3") (pin "3") (pinfunction "C_3") (pintype "passive"))
    )
    (net (code "42") (name "Net-(Q3-E)") (class "Default")
      (node (ref "Q3") (pin "2") (pinfunction "E_2") (pintype "passive"))
      (node (ref "R14") (pin "2") (pinfunction "2_2") (pintype "passive"))
      (node (ref "R50") (pin "1") (pinfunction "1_1") (pintype "passive"))
      (node (ref "R50") (pin "2") (pinfunction "ADJ_2") (pintype "passive"))
      (node (ref "R9") (pin "2") (pinfunction "2_2") (pintype "passive"))
    )
    (net (code "43") (name "Net-(Q4-B)") (class "Default")
      (node (ref "Q4") (pin "1") (pinfunction "B_1") (pintype "passive"))
      (node (ref "R23") (pin "1") (pinfunction "1_1") (pintype "passive"))
    )
    (net (code "44") (name "Net-(Q5-B)") (class "Default")
      (node (ref "Q5") (pin "1") (pinfunction "B_1") (pintype "passive"))
      (node (ref "R24") (pin "1") (pinfunction "1_1") (pintype "passive"))
    )
    (net (code "45") (name "Net-(Q6-B)") (class "Default")
      (node (ref "Q6") (pin "1") (pinfunction "B_1") (pintype "passive"))
      (node (ref "R4") (pin "1") (pinfunction "1_1") (pintype "passive"))
      (node (ref "R7") (pin "2") (pinfunction "2_2") (pintype "passive"))
    )
    (net (code "46") (name "Net-(Q7-D)") (class "Default")
      (node (ref "Q7") (pin "3") (pinfunction "D_3") (pintype "passive"))
      (node (ref "Q8") (pin "3") (pinfunction "D_3") (pintype "passive"))
    )
    (net (code "47") (name "Net-(Q7-G)") (class "Default")
      (node (ref "Q7") (pin "1") (pinfunction "G_1") (pintype "passive"))
      (node (ref "U2") (pin "3") (pinfunction "OC_3") (pintype "bidirectional"))
    )
    (net (code "48") (name "Net-(Q8-G)") (class "Default")
      (node (ref "Q8") (pin "1") (pinfunction "G_1") (pintype "passive"))
      (node (ref "U2") (pin "1") (pinfunction "OD_1") (pintype "bidirectional"))
    )
    (net (code "49") (name "Net-(Q8-S)") (class "Default")
      (node (ref "B3") (pin "-") (pinfunction "-_-") (pintype "bidirectional"))
      (node (ref "C23") (pin "2") (pinfunction "2_2") (pintype "passive"))
      (node (ref "Q8") (pin "2") (pinfunction "S_2") (pintype "passive"))
      (node (ref "U2") (pin "6") (pinfunction "VSS_6") (pintype "bidirectional"))
    )
    (net (code "50") (name "Net-(R10-Pad1)") (class "Default")
      (node (ref "R10") (pin "1") (pinfunction "1_1") (pintype "passive"))
      (node (ref "R26") (pin "1") (pinfunction "1_1") (pintype "passive"))
    )
    (net (code "51") (name "Net-(R10-Pad2)") (class "Default")
      (node (ref "R10") (pin "2") (pinfunction "2_2") (pintype "passive"))
      (node (ref "R2") (pin "1") (pinfunction "1_1") (pintype "passive"))
    )
    (net (code "52") (name "Net-(R26-Pad2)") (class "Default")
      (node (ref "R26") (pin "2") (pinfunction "2_2") (pintype "passive"))
      (node (ref "R27") (pin "1") (pinfunction "1_1") (pintype "passive"))
    )
    (net (code "53") (name "Net-(R27-Pad2)") (class "Default")
      (node (ref "R27") (pin "2") (pinfunction "2_2") (pintype "passive"))
      (node (ref "R51") (pin "1") (pinfunction "1_1") (pintype "passive"))
      (node (ref "R52") (pin "1") (pinfunction "1_1") (pintype "passive"))
      (node (ref "R53") (pin "1") (pinfunction "1_1") (pintype "passive"))
    )
    (net (code "54") (name "Net-(R29-Pad2)") (class "Default")
      (node (ref "R29") (pin "2") (pinfunction "2_2") (pintype "passive"))
      (node (ref "R33") (pin "2") (pinfunction "2_2") (pintype "passive"))
      (node (ref "R34") (pin "1") (pinfunction "1_1") (pintype "passive"))
    )
    (net (code "55") (name "Net-(R30-Pad2)") (class "Default")
      (node (ref "R30") (pin "2") (pinfunction "2_2") (pintype "passive"))
      (node (ref "R31") (pin "1") (pinfunction "1_1") (pintype "passive"))
    )
    (net (code "56") (name "Net-(R31-Pad2)") (class "Default")
      (node (ref "R31") (pin "2") (pinfunction "2_2") (pintype "passive"))
      (node (ref "R32") (pin "1") (pinfunction "1_1") (pintype "passive"))
    )
    (net (code "57") (name "Net-(R32-Pad2)") (class "Default")
      (node (ref "R32") (pin "2") (pinfunction "2_2") (pintype "passive"))
      (node (ref "R33") (pin "1") (pinfunction "1_1") (pintype "passive"))
    )
    (net (code "58") (name "Net-(R46-Pad2)") (class "Default")
      (node (ref "R46") (pin "2") (pinfunction "2_2") (pintype "passive"))
      (node (ref "R47") (pin "1") (pinfunction "1_1") (pintype "passive"))
    )
    (net (code "59") (name "Net-(R47-Pad2)") (class "Default")
      (node (ref "R47") (pin "2") (pinfunction "2_2") (pintype "passive"))
      (node (ref "R48") (pin "2") (pinfunction "2_2") (pintype "passive"))
      (node (ref "R49") (pin "2") (pinfunction "2_2") (pintype "passive"))
    )
    (net (code "60") (name "Net-(R50-2)") (class "Default")
      (node (ref "R50") (pin "3") (pinfunction "2_3") (pintype "passive"))
      (node (ref "R54") (pin "2") (pinfunction "2_2") (pintype "passive"))
      (node (ref "R55") (pin "2") (pinfunction "2_2") (pintype "passive"))
      (node (ref "R9") (pin "1") (pinfunction "1_1") (pintype "passive"))
    )
    (net (code "61") (name "Net-(SW1-COM)") (class "Default")
      (node (ref "C22") (pin "1") (pinfunction "1_1") (pintype "passive"))
      (node (ref "C23") (pin "1") (pinfunction "1_1") (pintype "passive"))
      (node (ref "C28") (pin "1") (pinfunction "1_1") (pintype "passive"))
      (node (ref "C31") (pin "1") (pinfunction "1_1") (pintype "passive"))
      (node (ref "F1") (pin "P$2") (pinfunction "P$2_P$2") (pintype "bidirectional"))
      (node (ref "SW1") (pin "2") (pinfunction "COM_2") (pintype "bidirectional"))
      (node (ref "U2") (pin "5") (pinfunction "VDD_5") (pintype "bidirectional"))
      (node (ref "U7") (pin "10") (pinfunction "BAT_10") (pintype "bidirectional"))
    )
    (net (code "62") (name "Net-(U1-CV)") (class "Default")
      (node (ref "C27") (pin "1") (pinfunction "1_1") (pintype "passive"))
      (node (ref "U1") (pin "5") (pinfunction "CV_5") (pintype "passive"))
    )
    (net (code "63") (name "Net-(U1-OUT)") (class "Default")
      (node (ref "R28") (pin "2") (pinfunction "2_2") (pintype "passive"))
      (node (ref "R5") (pin "2") (pinfunction "2_2") (pintype "passive"))
      (node (ref "U1") (pin "3") (pinfunction "OUT_3") (pintype "output"))
    )
    (net (code "64") (name "Net-(U2-CS)") (class "Default")
      (node (ref "R3") (pin "2") (pinfunction "2_2") (pintype "passive"))
      (node (ref "U2") (pin "2") (pinfunction "CS_2") (pintype "bidirectional"))
    )
    (net (code "65") (name "Net-(U4-D+)") (class "Default")
      (node (ref "R12") (pin "2") (pinfunction "2_2") (pintype "passive"))
      (node (ref "U4") (pin "4") (pinfunction "D+_4") (pintype "bidirectional"))
    )
    (net (code "66") (name "Net-(U4-D-)") (class "Default")
      (node (ref "R11") (pin "2") (pinfunction "2_2") (pintype "passive"))
      (node (ref "U4") (pin "5") (pinfunction "D-_5") (pintype "bidirectional"))
    )
    (net (code "67") (name "Net-(U4-VBUS)") (class "Default")
      (node (ref "R13") (pin "1") (pinfunction "1_1") (pintype "passive"))
      (node (ref "R15") (pin "2") (pinfunction "2_2") (pintype "passive"))
      (node (ref "U4") (pin "8") (pinfunction "VBUS_8") (pintype "power_in"))
    )
    (net (code "68") (name "Net-(U4-~{RST})") (class "Default")
      (node (ref "R18") (pin "1") (pinfunction "1_1") (pintype "passive"))
      (node (ref "U4") (pin "9") (pinfunction "~{RST}_9") (pintype "input"))
    )
    (net (code "69") (name "Net-(U4-~{SUSPENDB})") (class "Default")
      (node (ref "R19") (pin "2") (pinfunction "2_2") (pintype "passive"))
      (node (ref "U4") (pin "11") (pinfunction "~{SUSPENDB}_11") (pintype "output"))
    )
    (net (code "70") (name "Net-(U6-EN)") (class "Default")
      (node (ref "C24") (pin "1") (pinfunction "1_1") (pintype "passive"))
      (node (ref "R43") (pin "1") (pinfunction "1_1") (pintype "passive"))
      (node (ref "U6") (pin "6") (pinfunction "EN_6") (pintype "bidirectional"))
      (node (ref "U6") (pin "7") (pinfunction "PS/SYNC_7") (pintype "bidirectional"))
      (node (ref "U6") (pin "8") (pinfunction "VINA_8") (pintype "bidirectional"))
    )
    (net (code "71") (name "Net-(U6-FB)") (class "Default")
      (node (ref "R41") (pin "2") (pinfunction "2_2") (pintype "passive"))
      (node (ref "R42") (pin "2") (pinfunction "2_2") (pintype "passive"))
      (node (ref "U6") (pin "10") (pinfunction "FB_10") (pintype "bidirectional"))
    )
    (net (code "72") (name "Net-(U7-CHG)") (class "Default")
      (node (ref "R40") (pin "1") (pinfunction "1_1") (pintype "passive"))
      (node (ref "U7") (pin "2") (pinfunction "CHG_2") (pintype "bidirectional"))
    )
    (net (code "73") (name "Net-(U7-IBF)") (class "Default")
      (node (ref "R39") (pin "2") (pinfunction "2_2") (pintype "passive"))
      (node (ref "U7") (pin "8") (pinfunction "IBF_8") (pintype "bidirectional"))
    )
    (net (code "74") (name "Net-(U7-ISET)") (class "Default")
      (node (ref "R35") (pin "2") (pinfunction "2_2") (pintype "passive"))
      (node (ref "U7") (pin "9") (pinfunction "ISET_9") (pintype "bidirectional"))
    )
    (net (code "75") (name "Net-(U7-NTC)") (class "Default")
      (node (ref "R45") (pin "2") (pinfunction "2_2") (pintype "passive"))
      (node (ref "U7") (pin "5") (pinfunction "NTC_5") (pintype "bidirectional"))
    )
    (net (code "76") (name "PIEZO") (class "Default")
      (node (ref "B1") (pin "1") (pinfunction "1_1") (pintype "passive"))
      (node (ref "U3") (pin "29") (pinfunction "IO5_29") (pintype "bidirectional"))
    )
    (net (code "77") (name "RTS") (class "Default")
      (node (ref "Q4") (pin "2") (pinfunction "E_2") (pintype "passive"))
      (node (ref "R24") (pin "2") (pinfunction "2_2") (pintype "passive"))
      (node (ref "U4") (pin "24") (pinfunction "RTS_24") (pintype "output"))
    )
    (net (code "78") (name "RXD0") (class "Default")
      (node (ref "R21") (pin "2") (pinfunction "2_2") (pintype "passive"))
      (node (ref "U3") (pin "34") (pinfunction "RXD0_34") (pintype "bidirectional"))
    )
    (net (code "79") (name "TXD0") (class "Default")
      (node (ref "R20") (pin "2") (pinfunction "2_2") (pintype "passive"))
      (node (ref "R48") (pin "1") (pinfunction "1_1") (pintype "passive"))
      (node (ref "U3") (pin "35") (pinfunction "TXD0_35") (pintype "bidirectional"))
    )
    (net (code "80") (name "VUSBIN") (class "Default")
      (node (ref "C21") (pin "1") (pinfunction "1_1") (pintype "passive"))
      (node (ref "C7") (pin "1") (pinfunction "1_1") (pintype "passive"))
      (node (ref "D2") (pin "A") (pinfunction "A_A") (pintype "bidirectional"))
      (node (ref "J2") (pin "A4") (pinfunction "VCC_A4") (pintype "bidirectional"))
      (node (ref "J2") (pin "A9") (pinfunction "VCC_A9") (pintype "bidirectional"))
      (node (ref "J2") (pin "B4") (pinfunction "VCC_B4") (pintype "bidirectional"))
      (node (ref "J2") (pin "B9") (pinfunction "VCC_B9") (pintype "bidirectional"))
      (node (ref "R13") (pin "2") (pinfunction "2_2") (pintype "passive"))
      (node (ref "U7") (pin "1") (pinfunction "VIN_1") (pintype "bidirectional"))
    )
    (net (code "81") (name "unconnected-(J2-SBV2-PadB8)") (class "Default")
      (node (ref "J2") (pin "B8") (pinfunction "SBV2_B8") (pintype "bidirectional"))
    )
    (net (code "82") (name "unconnected-(SW1-P$2-Pad1)") (class "Default")
      (node (ref "SW1") (pin "1") (pinfunction "P$2_1") (pintype "bidirectional"))
    )
    (net (code "83") (name "unconnected-(U3-IO12-Pad14)") (class "Default")
      (node (ref "U3") (pin "14") (pinfunction "IO12_14") (pintype "bidirectional"))
    )
    (net (code "84") (name "unconnected-(U3-IO14-Pad13)") (class "Default")
      (node (ref "U3") (pin "13") (pinfunction "IO14_13") (pintype "bidirectional"))
    )
    (net (code "85") (name "unconnected-(U3-IO15-Pad23)") (class "Default")
      (node (ref "U3") (pin "23") (pinfunction "IO15_23") (pintype "bidirectional"))
    )
    (net (code "86") (name "unconnected-(U3-IO21-Pad33)") (class "Default")
      (node (ref "U3") (pin "33") (pinfunction "IO21_33") (pintype "bidirectional"))
    )
    (net (code "87") (name "unconnected-(U3-IO23-Pad37)") (class "Default")
      (node (ref "U3") (pin "37") (pinfunction "IO23_37") (pintype "bidirectional"))
    )
    (net (code "88") (name "unconnected-(U3-IO25-Pad10)") (class "Default")
      (node (ref "U3") (pin "10") (pinfunction "IO25_10") (pintype "bidirectional"))
    )
    (net (code "89") (name "unconnected-(U3-IO26-Pad11)") (class "Default")
      (node (ref "U3") (pin "11") (pinfunction "IO26_11") (pintype "bidirectional"))
    )
    (net (code "90") (name "unconnected-(U3-IO27-Pad12)") (class "Default")
      (node (ref "U3") (pin "12") (pinfunction "IO27_12") (pintype "bidirectional"))
    )
    (net (code "91") (name "unconnected-(U3-IO32-Pad8)") (class "Default")
      (node (ref "U3") (pin "8") (pinfunction "IO32_8") (pintype "bidirectional"))
    )
    (net (code "92") (name "unconnected-(U3-IO33-Pad9)") (class "Default")
      (node (ref "U3") (pin "9") (pinfunction "IO33_9") (pintype "bidirectional"))
    )
    (net (code "93") (name "unconnected-(U3-IO34-Pad6)") (class "Default")
      (node (ref "U3") (pin "6") (pinfunction "IO34_6") (pintype "input"))
    )
    (net (code "94") (name "unconnected-(U3-IO35-Pad7)") (class "Default")
      (node (ref "U3") (pin "7") (pinfunction "IO35_7") (pintype "input"))
    )
    (net (code "95") (name "unconnected-(U3-SCK{slash}CLK-Pad20)") (class "Default")
      (node (ref "U3") (pin "20") (pinfunction "SCK/CLK_20") (pintype "bidirectional"))
    )
    (net (code "96") (name "unconnected-(U3-SCS{slash}CMD-Pad19)") (class "Default")
      (node (ref "U3") (pin "19") (pinfunction "SCS/CMD_19") (pintype "bidirectional"))
    )
    (net (code "97") (name "unconnected-(U3-SDI{slash}SD1-Pad22)") (class "Default")
      (node (ref "U3") (pin "22") (pinfunction "SDI/SD1_22") (pintype "bidirectional"))
    )
    (net (code "98") (name "unconnected-(U3-SDO{slash}SD0-Pad21)") (class "Default")
      (node (ref "U3") (pin "21") (pinfunction "SDO/SD0_21") (pintype "bidirectional"))
    )
    (net (code "99") (name "unconnected-(U3-SENSOR_VN-Pad5)") (class "Default")
      (node (ref "U3") (pin "5") (pinfunction "SENSOR_VN_5") (pintype "input"))
    )
    (net (code "100") (name "unconnected-(U3-SENSOR_VP-Pad4)") (class "Default")
      (node (ref "U3") (pin "4") (pinfunction "SENSOR_VP_4") (pintype "input"))
    )
    (net (code "101") (name "unconnected-(U3-SHD{slash}SD2-Pad17)") (class "Default")
      (node (ref "U3") (pin "17") (pinfunction "SHD/SD2_17") (pintype "bidirectional"))
    )
    (net (code "102") (name "unconnected-(U3-SWP{slash}SD3-Pad18)") (class "Default")
      (node (ref "U3") (pin "18") (pinfunction "SWP/SD3_18") (pintype "bidirectional"))
    )
    (net (code "103") (name "unconnected-(U4-CHR0-Pad15)") (class "Default")
      (node (ref "U4") (pin "15") (pinfunction "CHR0_15") (pintype "output"))
    )
    (net (code "104") (name "unconnected-(U4-CHR1-Pad14)") (class "Default")
      (node (ref "U4") (pin "14") (pinfunction "CHR1_14") (pintype "output"))
    )
    (net (code "105") (name "unconnected-(U4-CHREN-Pad13)") (class "Default")
      (node (ref "U4") (pin "13") (pinfunction "CHREN_13") (pintype "output"))
    )
    (net (code "106") (name "unconnected-(U4-CTS-Pad23)") (class "Default")
      (node (ref "U4") (pin "23") (pinfunction "CTS_23") (pintype "input"))
    )
    (net (code "107") (name "unconnected-(U4-DCD-Pad1)") (class "Default")
      (node (ref "U4") (pin "1") (pinfunction "DCD_1") (pintype "input"))
    )
    (net (code "108") (name "unconnected-(U4-DSR-Pad27)") (class "Default")
      (node (ref "U4") (pin "27") (pinfunction "DSR_27") (pintype "input"))
    )
    (net (code "109") (name "unconnected-(U4-GPIO.0{slash}TXT-Pad19)") (class "Default")
      (node (ref "U4") (pin "19") (pinfunction "GPIO.0/TXT_19") (pintype "bidirectional"))
    )
    (net (code "110") (name "unconnected-(U4-GPIO.1{slash}RXT-Pad18)") (class "Default")
      (node (ref "U4") (pin "18") (pinfunction "GPIO.1/RXT_18") (pintype "bidirectional"))
    )
    (net (code "111") (name "unconnected-(U4-GPIO.2{slash}RS485-Pad17)") (class "Default")
      (node (ref "U4") (pin "17") (pinfunction "GPIO.2/RS485_17") (pintype "bidirectional"))
    )
    (net (code "112") (name "unconnected-(U4-GPIO.3{slash}WAKEUP-Pad16)") (class "Default")
      (node (ref "U4") (pin "16") (pinfunction "GPIO.3/WAKEUP_16") (pintype "bidirectional"))
    )
    (net (code "113") (name "unconnected-(U4-GPIO.4-Pad22)") (class "Default")
      (node (ref "U4") (pin "22") (pinfunction "GPIO.4_22") (pintype "bidirectional"))
    )
    (net (code "114") (name "unconnected-(U4-GPIO.5-Pad21)") (class "Default")
      (node (ref "U4") (pin "21") (pinfunction "GPIO.5_21") (pintype "bidirectional"))
    )
    (net (code "115") (name "unconnected-(U4-GPIO.6-Pad20)") (class "Default")
      (node (ref "U4") (pin "20") (pinfunction "GPIO.6_20") (pintype "bidirectional"))
    )
    (net (code "116") (name "unconnected-(U4-NC-Pad10)") (class "Default")
      (node (ref "U4") (pin "10") (pinfunction "NC_10") (pintype "no_connect"))
    )
    (net (code "117") (name "unconnected-(U4-RI{slash}CLK-Pad2)") (class "Default")
      (node (ref "U4") (pin "2") (pinfunction "RI/CLK_2") (pintype "bidirectional"))
    )
    (net (code "118") (name "unconnected-(U4-SUSPEND-Pad12)") (class "Default")
      (node (ref "U4") (pin "12") (pinfunction "SUSPEND_12") (pintype "output"))
    )
    (net (code "119") (name "unconnected-(U7-NC-Pad7)") (class "Default")
      (node (ref "U7") (pin "7") (pinfunction "NC_7") (pintype "bidirectional"))
    )
    (net (code "120") (name "unconnected-(U7-PG-Pad3)") (class "Default")
      (node (ref "U7") (pin "3") (pinfunction "PG_3") (pintype "bidirectional"))
    )
  )
)
